# TX_FlexiConnectors.net
KiCad netlist of a schematic drawn in Altium Designer
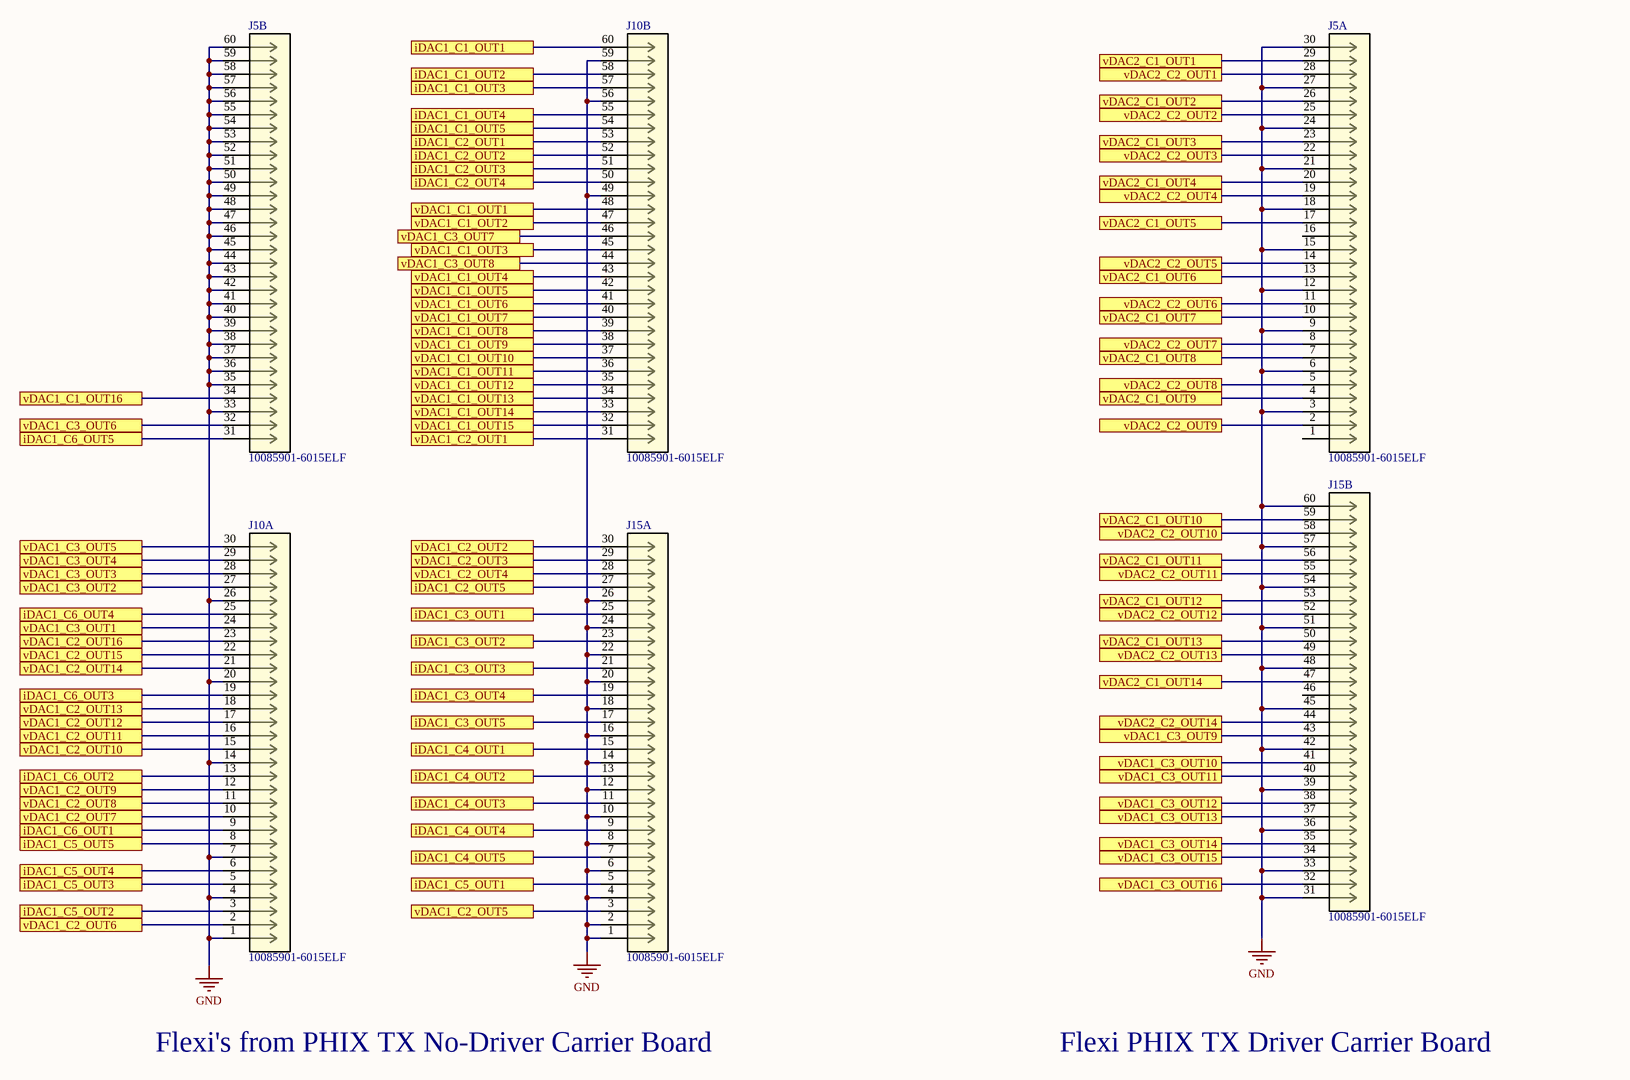
[diagram p0: TX_FlexiConnectors.SchDoc]

(export (version "E")
  (design (tool "Eeschema 10.0.6"))
  (components
    (comp (ref "J5")
      (value "10085901-6015ELF")
      (footprint "CONN_10085901-6015ELF_AMP")
      (description "No Description Available")
      (fields (field (name "COPYRIGHT") "Copyright (C) 2018 Accelerated Designs. All rights reserved"))
      (libsource (lib "xDAC_Carrier") (part "10085901-6015ELF"))
    )
    (comp (ref "J10")
      (value "10085901-6015ELF")
      (footprint "CONN_10085901-6015ELF_AMP")
      (description "No Description Available")
      (fields (field (name "COPYRIGHT") "Copyright (C) 2018 Accelerated Designs. All rights reserved"))
      (libsource (lib "xDAC_Carrier") (part "10085901-6015ELF"))
    )
    (comp (ref "J15")
      (value "10085901-6015ELF")
      (footprint "CONN_10085901-6015ELF_AMP")
      (description "No Description Available")
      (fields (field (name "COPYRIGHT") "Copyright (C) 2018 Accelerated Designs. All rights reserved"))
      (libsource (lib "xDAC_Carrier") (part "10085901-6015ELF"))
    )
  )
  (nets
    (net (code "1") (name "/iDAC1_C1_OUT1") (class "Default")
      (node (ref "J10") (pin "60") (pinfunction "60_60") (pintype "passive"))
    )
    (net (code "2") (name "/iDAC1_C1_OUT2") (class "Default")
      (node (ref "J10") (pin "58") (pinfunction "58_58") (pintype "passive"))
    )
    (net (code "3") (name "/iDAC1_C1_OUT3") (class "Default")
      (node (ref "J10") (pin "57") (pinfunction "57_57") (pintype "passive"))
    )
    (net (code "4") (name "/iDAC1_C1_OUT4") (class "Default")
      (node (ref "J10") (pin "55") (pinfunction "55_55") (pintype "passive"))
    )
    (net (code "5") (name "/iDAC1_C1_OUT5") (class "Default")
      (node (ref "J10") (pin "54") (pinfunction "54_54") (pintype "passive"))
    )
    (net (code "6") (name "/iDAC1_C2_OUT1") (class "Default")
      (node (ref "J10") (pin "53") (pinfunction "53_53") (pintype "passive"))
    )
    (net (code "7") (name "/iDAC1_C2_OUT2") (class "Default")
      (node (ref "J10") (pin "52") (pinfunction "52_52") (pintype "passive"))
    )
    (net (code "8") (name "/iDAC1_C2_OUT3") (class "Default")
      (node (ref "J10") (pin "51") (pinfunction "51_51") (pintype "passive"))
    )
    (net (code "9") (name "/iDAC1_C2_OUT4") (class "Default")
      (node (ref "J10") (pin "50") (pinfunction "50_50") (pintype "passive"))
    )
    (net (code "10") (name "/iDAC1_C2_OUT5") (class "Default")
      (node (ref "J15") (pin "27") (pinfunction "27_27") (pintype "passive"))
    )
    (net (code "11") (name "/iDAC1_C3_OUT1") (class "Default")
      (node (ref "J15") (pin "25") (pinfunction "25_25") (pintype "passive"))
    )
    (net (code "12") (name "/iDAC1_C3_OUT2") (class "Default")
      (node (ref "J15") (pin "23") (pinfunction "23_23") (pintype "passive"))
    )
    (net (code "13") (name "/iDAC1_C3_OUT3") (class "Default")
      (node (ref "J15") (pin "21") (pinfunction "21_21") (pintype "passive"))
    )
    (net (code "14") (name "/iDAC1_C3_OUT4") (class "Default")
      (node (ref "J15") (pin "19") (pinfunction "19_19") (pintype "passive"))
    )
    (net (code "15") (name "/iDAC1_C3_OUT5") (class "Default")
      (node (ref "J15") (pin "17") (pinfunction "17_17") (pintype "passive"))
    )
    (net (code "16") (name "/iDAC1_C4_OUT1") (class "Default")
      (node (ref "J15") (pin "15") (pinfunction "15_15") (pintype "passive"))
    )
    (net (code "17") (name "/iDAC1_C4_OUT2") (class "Default")
      (node (ref "J15") (pin "13") (pinfunction "13_13") (pintype "passive"))
    )
    (net (code "18") (name "/iDAC1_C4_OUT3") (class "Default")
      (node (ref "J15") (pin "11") (pinfunction "11_11") (pintype "passive"))
    )
    (net (code "19") (name "/iDAC1_C4_OUT4") (class "Default")
      (node (ref "J15") (pin "9") (pinfunction "9_9") (pintype "passive"))
    )
    (net (code "20") (name "/iDAC1_C4_OUT5") (class "Default")
      (node (ref "J15") (pin "7") (pinfunction "7_7") (pintype "passive"))
    )
    (net (code "21") (name "/iDAC1_C5_OUT1") (class "Default")
      (node (ref "J15") (pin "5") (pinfunction "5_5") (pintype "passive"))
    )
    (net (code "22") (name "/iDAC1_C5_OUT2") (class "Default")
      (node (ref "J10") (pin "3") (pinfunction "3_3") (pintype "passive"))
    )
    (net (code "23") (name "/iDAC1_C5_OUT3") (class "Default")
      (node (ref "J10") (pin "5") (pinfunction "5_5") (pintype "passive"))
    )
    (net (code "24") (name "/iDAC1_C5_OUT4") (class "Default")
      (node (ref "J10") (pin "6") (pinfunction "6_6") (pintype "passive"))
    )
    (net (code "25") (name "/iDAC1_C5_OUT5") (class "Default")
      (node (ref "J10") (pin "8") (pinfunction "8_8") (pintype "passive"))
    )
    (net (code "26") (name "/iDAC1_C6_OUT1") (class "Default")
      (node (ref "J10") (pin "9") (pinfunction "9_9") (pintype "passive"))
    )
    (net (code "27") (name "/iDAC1_C6_OUT2") (class "Default")
      (node (ref "J10") (pin "13") (pinfunction "13_13") (pintype "passive"))
    )
    (net (code "28") (name "/iDAC1_C6_OUT3") (class "Default")
      (node (ref "J10") (pin "19") (pinfunction "19_19") (pintype "passive"))
    )
    (net (code "29") (name "/iDAC1_C6_OUT4") (class "Default")
      (node (ref "J10") (pin "25") (pinfunction "25_25") (pintype "passive"))
    )
    (net (code "30") (name "/iDAC1_C6_OUT5") (class "Default")
      (node (ref "J5") (pin "31") (pinfunction "31_31") (pintype "passive"))
    )
    (net (code "31") (name "/vDAC1_C1_OUT1") (class "Default")
      (node (ref "J10") (pin "48") (pinfunction "48_48") (pintype "passive"))
    )
    (net (code "32") (name "/vDAC1_C1_OUT2") (class "Default")
      (node (ref "J10") (pin "47") (pinfunction "47_47") (pintype "passive"))
    )
    (net (code "33") (name "/vDAC1_C1_OUT3") (class "Default")
      (node (ref "J10") (pin "45") (pinfunction "45_45") (pintype "passive"))
    )
    (net (code "34") (name "/vDAC1_C1_OUT4") (class "Default")
      (node (ref "J10") (pin "43") (pinfunction "43_43") (pintype "passive"))
    )
    (net (code "35") (name "/vDAC1_C1_OUT5") (class "Default")
      (node (ref "J10") (pin "42") (pinfunction "42_42") (pintype "passive"))
    )
    (net (code "36") (name "/vDAC1_C1_OUT6") (class "Default")
      (node (ref "J10") (pin "41") (pinfunction "41_41") (pintype "passive"))
    )
    (net (code "37") (name "/vDAC1_C1_OUT7") (class "Default")
      (node (ref "J10") (pin "40") (pinfunction "40_40") (pintype "passive"))
    )
    (net (code "38") (name "/vDAC1_C1_OUT8") (class "Default")
      (node (ref "J10") (pin "39") (pinfunction "39_39") (pintype "passive"))
    )
    (net (code "39") (name "/vDAC1_C1_OUT9") (class "Default")
      (node (ref "J10") (pin "38") (pinfunction "38_38") (pintype "passive"))
    )
    (net (code "40") (name "/vDAC1_C1_OUT10") (class "Default")
      (node (ref "J10") (pin "37") (pinfunction "37_37") (pintype "passive"))
    )
    (net (code "41") (name "/vDAC1_C1_OUT11") (class "Default")
      (node (ref "J10") (pin "36") (pinfunction "36_36") (pintype "passive"))
    )
    (net (code "42") (name "/vDAC1_C1_OUT12") (class "Default")
      (node (ref "J10") (pin "35") (pinfunction "35_35") (pintype "passive"))
    )
    (net (code "43") (name "/vDAC1_C1_OUT13") (class "Default")
      (node (ref "J10") (pin "34") (pinfunction "34_34") (pintype "passive"))
    )
    (net (code "44") (name "/vDAC1_C1_OUT14") (class "Default")
      (node (ref "J10") (pin "33") (pinfunction "33_33") (pintype "passive"))
    )
    (net (code "45") (name "/vDAC1_C1_OUT15") (class "Default")
      (node (ref "J10") (pin "32") (pinfunction "32_32") (pintype "passive"))
    )
    (net (code "46") (name "/vDAC1_C1_OUT16") (class "Default")
      (node (ref "J5") (pin "34") (pinfunction "34_34") (pintype "passive"))
    )
    (net (code "47") (name "/vDAC1_C2_OUT1") (class "Default")
      (node (ref "J10") (pin "31") (pinfunction "31_31") (pintype "passive"))
    )
    (net (code "48") (name "/vDAC1_C2_OUT2") (class "Default")
      (node (ref "J15") (pin "30") (pinfunction "30_30") (pintype "passive"))
    )
    (net (code "49") (name "/vDAC1_C2_OUT3") (class "Default")
      (node (ref "J15") (pin "29") (pinfunction "29_29") (pintype "passive"))
    )
    (net (code "50") (name "/vDAC1_C2_OUT4") (class "Default")
      (node (ref "J15") (pin "28") (pinfunction "28_28") (pintype "passive"))
    )
    (net (code "51") (name "/vDAC1_C2_OUT5") (class "Default")
      (node (ref "J15") (pin "3") (pinfunction "3_3") (pintype "passive"))
    )
    (net (code "52") (name "/vDAC1_C2_OUT6") (class "Default")
      (node (ref "J10") (pin "2") (pinfunction "2_2") (pintype "passive"))
    )
    (net (code "53") (name "/vDAC1_C2_OUT7") (class "Default")
      (node (ref "J10") (pin "10") (pinfunction "10_10") (pintype "passive"))
    )
    (net (code "54") (name "/vDAC1_C2_OUT8") (class "Default")
      (node (ref "J10") (pin "11") (pinfunction "11_11") (pintype "passive"))
    )
    (net (code "55") (name "/vDAC1_C2_OUT9") (class "Default")
      (node (ref "J10") (pin "12") (pinfunction "12_12") (pintype "passive"))
    )
    (net (code "56") (name "/vDAC1_C2_OUT10") (class "Default")
      (node (ref "J10") (pin "15") (pinfunction "15_15") (pintype "passive"))
    )
    (net (code "57") (name "/vDAC1_C2_OUT11") (class "Default")
      (node (ref "J10") (pin "16") (pinfunction "16_16") (pintype "passive"))
    )
    (net (code "58") (name "/vDAC1_C2_OUT12") (class "Default")
      (node (ref "J10") (pin "17") (pinfunction "17_17") (pintype "passive"))
    )
    (net (code "59") (name "/vDAC1_C2_OUT13") (class "Default")
      (node (ref "J10") (pin "18") (pinfunction "18_18") (pintype "passive"))
    )
    (net (code "60") (name "/vDAC1_C2_OUT14") (class "Default")
      (node (ref "J10") (pin "21") (pinfunction "21_21") (pintype "passive"))
    )
    (net (code "61") (name "/vDAC1_C2_OUT15") (class "Default")
      (node (ref "J10") (pin "22") (pinfunction "22_22") (pintype "passive"))
    )
    (net (code "62") (name "/vDAC1_C2_OUT16") (class "Default")
      (node (ref "J10") (pin "23") (pinfunction "23_23") (pintype "passive"))
    )
    (net (code "63") (name "/vDAC1_C3_OUT1") (class "Default")
      (node (ref "J10") (pin "24") (pinfunction "24_24") (pintype "passive"))
    )
    (net (code "64") (name "/vDAC1_C3_OUT2") (class "Default")
      (node (ref "J10") (pin "27") (pinfunction "27_27") (pintype "passive"))
    )
    (net (code "65") (name "/vDAC1_C3_OUT3") (class "Default")
      (node (ref "J10") (pin "28") (pinfunction "28_28") (pintype "passive"))
    )
    (net (code "66") (name "/vDAC1_C3_OUT4") (class "Default")
      (node (ref "J10") (pin "29") (pinfunction "29_29") (pintype "passive"))
    )
    (net (code "67") (name "/vDAC1_C3_OUT5") (class "Default")
      (node (ref "J10") (pin "30") (pinfunction "30_30") (pintype "passive"))
    )
    (net (code "68") (name "/vDAC1_C3_OUT6") (class "Default")
      (node (ref "J5") (pin "32") (pinfunction "32_32") (pintype "passive"))
    )
    (net (code "69") (name "/vDAC1_C3_OUT7") (class "Default")
      (node (ref "J10") (pin "46") (pinfunction "46_46") (pintype "passive"))
    )
    (net (code "70") (name "/vDAC1_C3_OUT8") (class "Default")
      (node (ref "J10") (pin "44") (pinfunction "44_44") (pintype "passive"))
    )
    (net (code "71") (name "/vDAC1_C3_OUT9") (class "Default")
      (node (ref "J15") (pin "43") (pinfunction "43_43") (pintype "passive"))
    )
    (net (code "72") (name "/vDAC1_C3_OUT10") (class "Default")
      (node (ref "J15") (pin "41") (pinfunction "41_41") (pintype "passive"))
    )
    (net (code "73") (name "/vDAC1_C3_OUT11") (class "Default")
      (node (ref "J15") (pin "40") (pinfunction "40_40") (pintype "passive"))
    )
    (net (code "74") (name "/vDAC1_C3_OUT12") (class "Default")
      (node (ref "J15") (pin "38") (pinfunction "38_38") (pintype "passive"))
    )
    (net (code "75") (name "/vDAC1_C3_OUT13") (class "Default")
      (node (ref "J15") (pin "37") (pinfunction "37_37") (pintype "passive"))
    )
    (net (code "76") (name "/vDAC1_C3_OUT14") (class "Default")
      (node (ref "J15") (pin "35") (pinfunction "35_35") (pintype "passive"))
    )
    (net (code "77") (name "/vDAC1_C3_OUT15") (class "Default")
      (node (ref "J15") (pin "34") (pinfunction "34_34") (pintype "passive"))
    )
    (net (code "78") (name "/vDAC1_C3_OUT16") (class "Default")
      (node (ref "J15") (pin "32") (pinfunction "32_32") (pintype "passive"))
    )
    (net (code "79") (name "/vDAC2_C1_OUT1") (class "Default")
      (node (ref "J5") (pin "29") (pinfunction "29_29") (pintype "passive"))
    )
    (net (code "80") (name "/vDAC2_C1_OUT2") (class "Default")
      (node (ref "J5") (pin "26") (pinfunction "26_26") (pintype "passive"))
    )
    (net (code "81") (name "/vDAC2_C1_OUT3") (class "Default")
      (node (ref "J5") (pin "23") (pinfunction "23_23") (pintype "passive"))
    )
    (net (code "82") (name "/vDAC2_C1_OUT4") (class "Default")
      (node (ref "J5") (pin "20") (pinfunction "20_20") (pintype "passive"))
    )
    (net (code "83") (name "/vDAC2_C1_OUT5") (class "Default")
      (node (ref "J5") (pin "17") (pinfunction "17_17") (pintype "passive"))
    )
    (net (code "84") (name "/vDAC2_C1_OUT6") (class "Default")
      (node (ref "J5") (pin "13") (pinfunction "13_13") (pintype "passive"))
    )
    (net (code "85") (name "/vDAC2_C1_OUT7") (class "Default")
      (node (ref "J5") (pin "10") (pinfunction "10_10") (pintype "passive"))
    )
    (net (code "86") (name "/vDAC2_C1_OUT8") (class "Default")
      (node (ref "J5") (pin "7") (pinfunction "7_7") (pintype "passive"))
    )
    (net (code "87") (name "/vDAC2_C1_OUT9") (class "Default")
      (node (ref "J5") (pin "4") (pinfunction "4_4") (pintype "passive"))
    )
    (net (code "88") (name "/vDAC2_C1_OUT10") (class "Default")
      (node (ref "J15") (pin "59") (pinfunction "59_59") (pintype "passive"))
    )
    (net (code "89") (name "/vDAC2_C1_OUT11") (class "Default")
      (node (ref "J15") (pin "56") (pinfunction "56_56") (pintype "passive"))
    )
    (net (code "90") (name "/vDAC2_C1_OUT12") (class "Default")
      (node (ref "J15") (pin "53") (pinfunction "53_53") (pintype "passive"))
    )
    (net (code "91") (name "/vDAC2_C1_OUT13") (class "Default")
      (node (ref "J15") (pin "50") (pinfunction "50_50") (pintype "passive"))
    )
    (net (code "92") (name "/vDAC2_C1_OUT14") (class "Default")
      (node (ref "J15") (pin "47") (pinfunction "47_47") (pintype "passive"))
    )
    (net (code "93") (name "/vDAC2_C2_OUT1") (class "Default")
      (node (ref "J5") (pin "28") (pinfunction "28_28") (pintype "passive"))
    )
    (net (code "94") (name "/vDAC2_C2_OUT2") (class "Default")
      (node (ref "J5") (pin "25") (pinfunction "25_25") (pintype "passive"))
    )
    (net (code "95") (name "/vDAC2_C2_OUT3") (class "Default")
      (node (ref "J5") (pin "22") (pinfunction "22_22") (pintype "passive"))
    )
    (net (code "96") (name "/vDAC2_C2_OUT4") (class "Default")
      (node (ref "J5") (pin "19") (pinfunction "19_19") (pintype "passive"))
    )
    (net (code "97") (name "/vDAC2_C2_OUT5") (class "Default")
      (node (ref "J5") (pin "14") (pinfunction "14_14") (pintype "passive"))
    )
    (net (code "98") (name "/vDAC2_C2_OUT6") (class "Default")
      (node (ref "J5") (pin "11") (pinfunction "11_11") (pintype "passive"))
    )
    (net (code "99") (name "/vDAC2_C2_OUT7") (class "Default")
      (node (ref "J5") (pin "8") (pinfunction "8_8") (pintype "passive"))
    )
    (net (code "100") (name "/vDAC2_C2_OUT8") (class "Default")
      (node (ref "J5") (pin "5") (pinfunction "5_5") (pintype "passive"))
    )
    (net (code "101") (name "/vDAC2_C2_OUT9") (class "Default")
      (node (ref "J5") (pin "2") (pinfunction "2_2") (pintype "passive"))
    )
    (net (code "102") (name "/vDAC2_C2_OUT10") (class "Default")
      (node (ref "J15") (pin "58") (pinfunction "58_58") (pintype "passive"))
    )
    (net (code "103") (name "/vDAC2_C2_OUT11") (class "Default")
      (node (ref "J15") (pin "55") (pinfunction "55_55") (pintype "passive"))
    )
    (net (code "104") (name "/vDAC2_C2_OUT12") (class "Default")
      (node (ref "J15") (pin "52") (pinfunction "52_52") (pintype "passive"))
    )
    (net (code "105") (name "/vDAC2_C2_OUT13") (class "Default")
      (node (ref "J15") (pin "49") (pinfunction "49_49") (pintype "passive"))
    )
    (net (code "106") (name "/vDAC2_C2_OUT14") (class "Default")
      (node (ref "J15") (pin "44") (pinfunction "44_44") (pintype "passive"))
    )
    (net (code "107") (name "GND") (class "Default")
      (node (ref "J10") (pin "1") (pinfunction "1_1") (pintype "passive"))
      (node (ref "J10") (pin "14") (pinfunction "14_14") (pintype "passive"))
      (node (ref "J10") (pin "20") (pinfunction "20_20") (pintype "passive"))
      (node (ref "J10") (pin "26") (pinfunction "26_26") (pintype "passive"))
      (node (ref "J10") (pin "4") (pinfunction "4_4") (pintype "passive"))
      (node (ref "J10") (pin "49") (pinfunction "49_49") (pintype "passive"))
      (node (ref "J10") (pin "56") (pinfunction "56_56") (pintype "passive"))
      (node (ref "J10") (pin "59") (pinfunction "59_59") (pintype "passive"))
      (node (ref "J10") (pin "7") (pinfunction "7_7") (pintype "passive"))
      (node (ref "J15") (pin "1") (pinfunction "1_1") (pintype "passive"))
      (node (ref "J15") (pin "10") (pinfunction "10_10") (pintype "passive"))
      (node (ref "J15") (pin "12") (pinfunction "12_12") (pintype "passive"))
      (node (ref "J15") (pin "14") (pinfunction "14_14") (pintype "passive"))
      (node (ref "J15") (pin "16") (pinfunction "16_16") (pintype "passive"))
      (node (ref "J15") (pin "18") (pinfunction "18_18") (pintype "passive"))
      (node (ref "J15") (pin "2") (pinfunction "2_2") (pintype "passive"))
      (node (ref "J15") (pin "20") (pinfunction "20_20") (pintype "passive"))
      (node (ref "J15") (pin "22") (pinfunction "22_22") (pintype "passive"))
      (node (ref "J15") (pin "24") (pinfunction "24_24") (pintype "passive"))
      (node (ref "J15") (pin "26") (pinfunction "26_26") (pintype "passive"))
      (node (ref "J15") (pin "31") (pinfunction "31_31") (pintype "passive"))
      (node (ref "J15") (pin "33") (pinfunction "33_33") (pintype "passive"))
      (node (ref "J15") (pin "36") (pinfunction "36_36") (pintype "passive"))
      (node (ref "J15") (pin "39") (pinfunction "39_39") (pintype "passive"))
      (node (ref "J15") (pin "4") (pinfunction "4_4") (pintype "passive"))
      (node (ref "J15") (pin "42") (pinfunction "42_42") (pintype "passive"))
      (node (ref "J15") (pin "45") (pinfunction "45_45") (pintype "passive"))
      (node (ref "J15") (pin "48") (pinfunction "48_48") (pintype "passive"))
      (node (ref "J15") (pin "51") (pinfunction "51_51") (pintype "passive"))
      (node (ref "J15") (pin "54") (pinfunction "54_54") (pintype "passive"))
      (node (ref "J15") (pin "57") (pinfunction "57_57") (pintype "passive"))
      (node (ref "J15") (pin "6") (pinfunction "6_6") (pintype "passive"))
      (node (ref "J15") (pin "60") (pinfunction "60_60") (pintype "passive"))
      (node (ref "J15") (pin "8") (pinfunction "8_8") (pintype "passive"))
      (node (ref "J5") (pin "12") (pinfunction "12_12") (pintype "passive"))
      (node (ref "J5") (pin "15") (pinfunction "15_15") (pintype "passive"))
      (node (ref "J5") (pin "18") (pinfunction "18_18") (pintype "passive"))
      (node (ref "J5") (pin "21") (pinfunction "21_21") (pintype "passive"))
      (node (ref "J5") (pin "24") (pinfunction "24_24") (pintype "passive"))
      (node (ref "J5") (pin "27") (pinfunction "27_27") (pintype "passive"))
      (node (ref "J5") (pin "3") (pinfunction "3_3") (pintype "passive"))
      (node (ref "J5") (pin "30") (pinfunction "30_30") (pintype "passive"))
      (node (ref "J5") (pin "33") (pinfunction "33_33") (pintype "passive"))
      (node (ref "J5") (pin "35") (pinfunction "35_35") (pintype "passive"))
      (node (ref "J5") (pin "36") (pinfunction "36_36") (pintype "passive"))
      (node (ref "J5") (pin "37") (pinfunction "37_37") (pintype "passive"))
      (node (ref "J5") (pin "38") (pinfunction "38_38") (pintype "passive"))
      (node (ref "J5") (pin "39") (pinfunction "39_39") (pintype "passive"))
      (node (ref "J5") (pin "40") (pinfunction "40_40") (pintype "passive"))
      (node (ref "J5") (pin "41") (pinfunction "41_41") (pintype "passive"))
      (node (ref "J5") (pin "42") (pinfunction "42_42") (pintype "passive"))
      (node (ref "J5") (pin "43") (pinfunction "43_43") (pintype "passive"))
      (node (ref "J5") (pin "44") (pinfunction "44_44") (pintype "passive"))
      (node (ref "J5") (pin "45") (pinfunction "45_45") (pintype "passive"))
      (node (ref "J5") (pin "46") (pinfunction "46_46") (pintype "passive"))
      (node (ref "J5") (pin "47") (pinfunction "47_47") (pintype "passive"))
      (node (ref "J5") (pin "48") (pinfunction "48_48") (pintype "passive"))
      (node (ref "J5") (pin "49") (pinfunction "49_49") (pintype "passive"))
      (node (ref "J5") (pin "50") (pinfunction "50_50") (pintype "passive"))
      (node (ref "J5") (pin "51") (pinfunction "51_51") (pintype "passive"))
      (node (ref "J5") (pin "52") (pinfunction "52_52") (pintype "passive"))
      (node (ref "J5") (pin "53") (pinfunction "53_53") (pintype "passive"))
      (node (ref "J5") (pin "54") (pinfunction "54_54") (pintype "passive"))
      (node (ref "J5") (pin "55") (pinfunction "55_55") (pintype "passive"))
      (node (ref "J5") (pin "56") (pinfunction "56_56") (pintype "passive"))
      (node (ref "J5") (pin "57") (pinfunction "57_57") (pintype "passive"))
      (node (ref "J5") (pin "58") (pinfunction "58_58") (pintype "passive"))
      (node (ref "J5") (pin "59") (pinfunction "59_59") (pintype "passive"))
      (node (ref "J5") (pin "6") (pinfunction "6_6") (pintype "passive"))
      (node (ref "J5") (pin "60") (pinfunction "60_60") (pintype "passive"))
      (node (ref "J5") (pin "9") (pinfunction "9_9") (pintype "passive"))
    )
    (net (code "108") (name "unconnected-(J5-Pad1)") (class "Default")
      (node (ref "J5") (pin "1") (pinfunction "1_1") (pintype "passive"))
    )
    (net (code "109") (name "unconnected-(J5-Pad16)") (class "Default")
      (node (ref "J5") (pin "16") (pinfunction "16_16") (pintype "passive"))
    )
    (net (code "110") (name "unconnected-(J15-Pad46)") (class "Default")
      (node (ref "J15") (pin "46") (pinfunction "46_46") (pintype "passive"))
    )
  )
)
